# connectors.net
KiCad netlist of a schematic drawn in Altium Designer
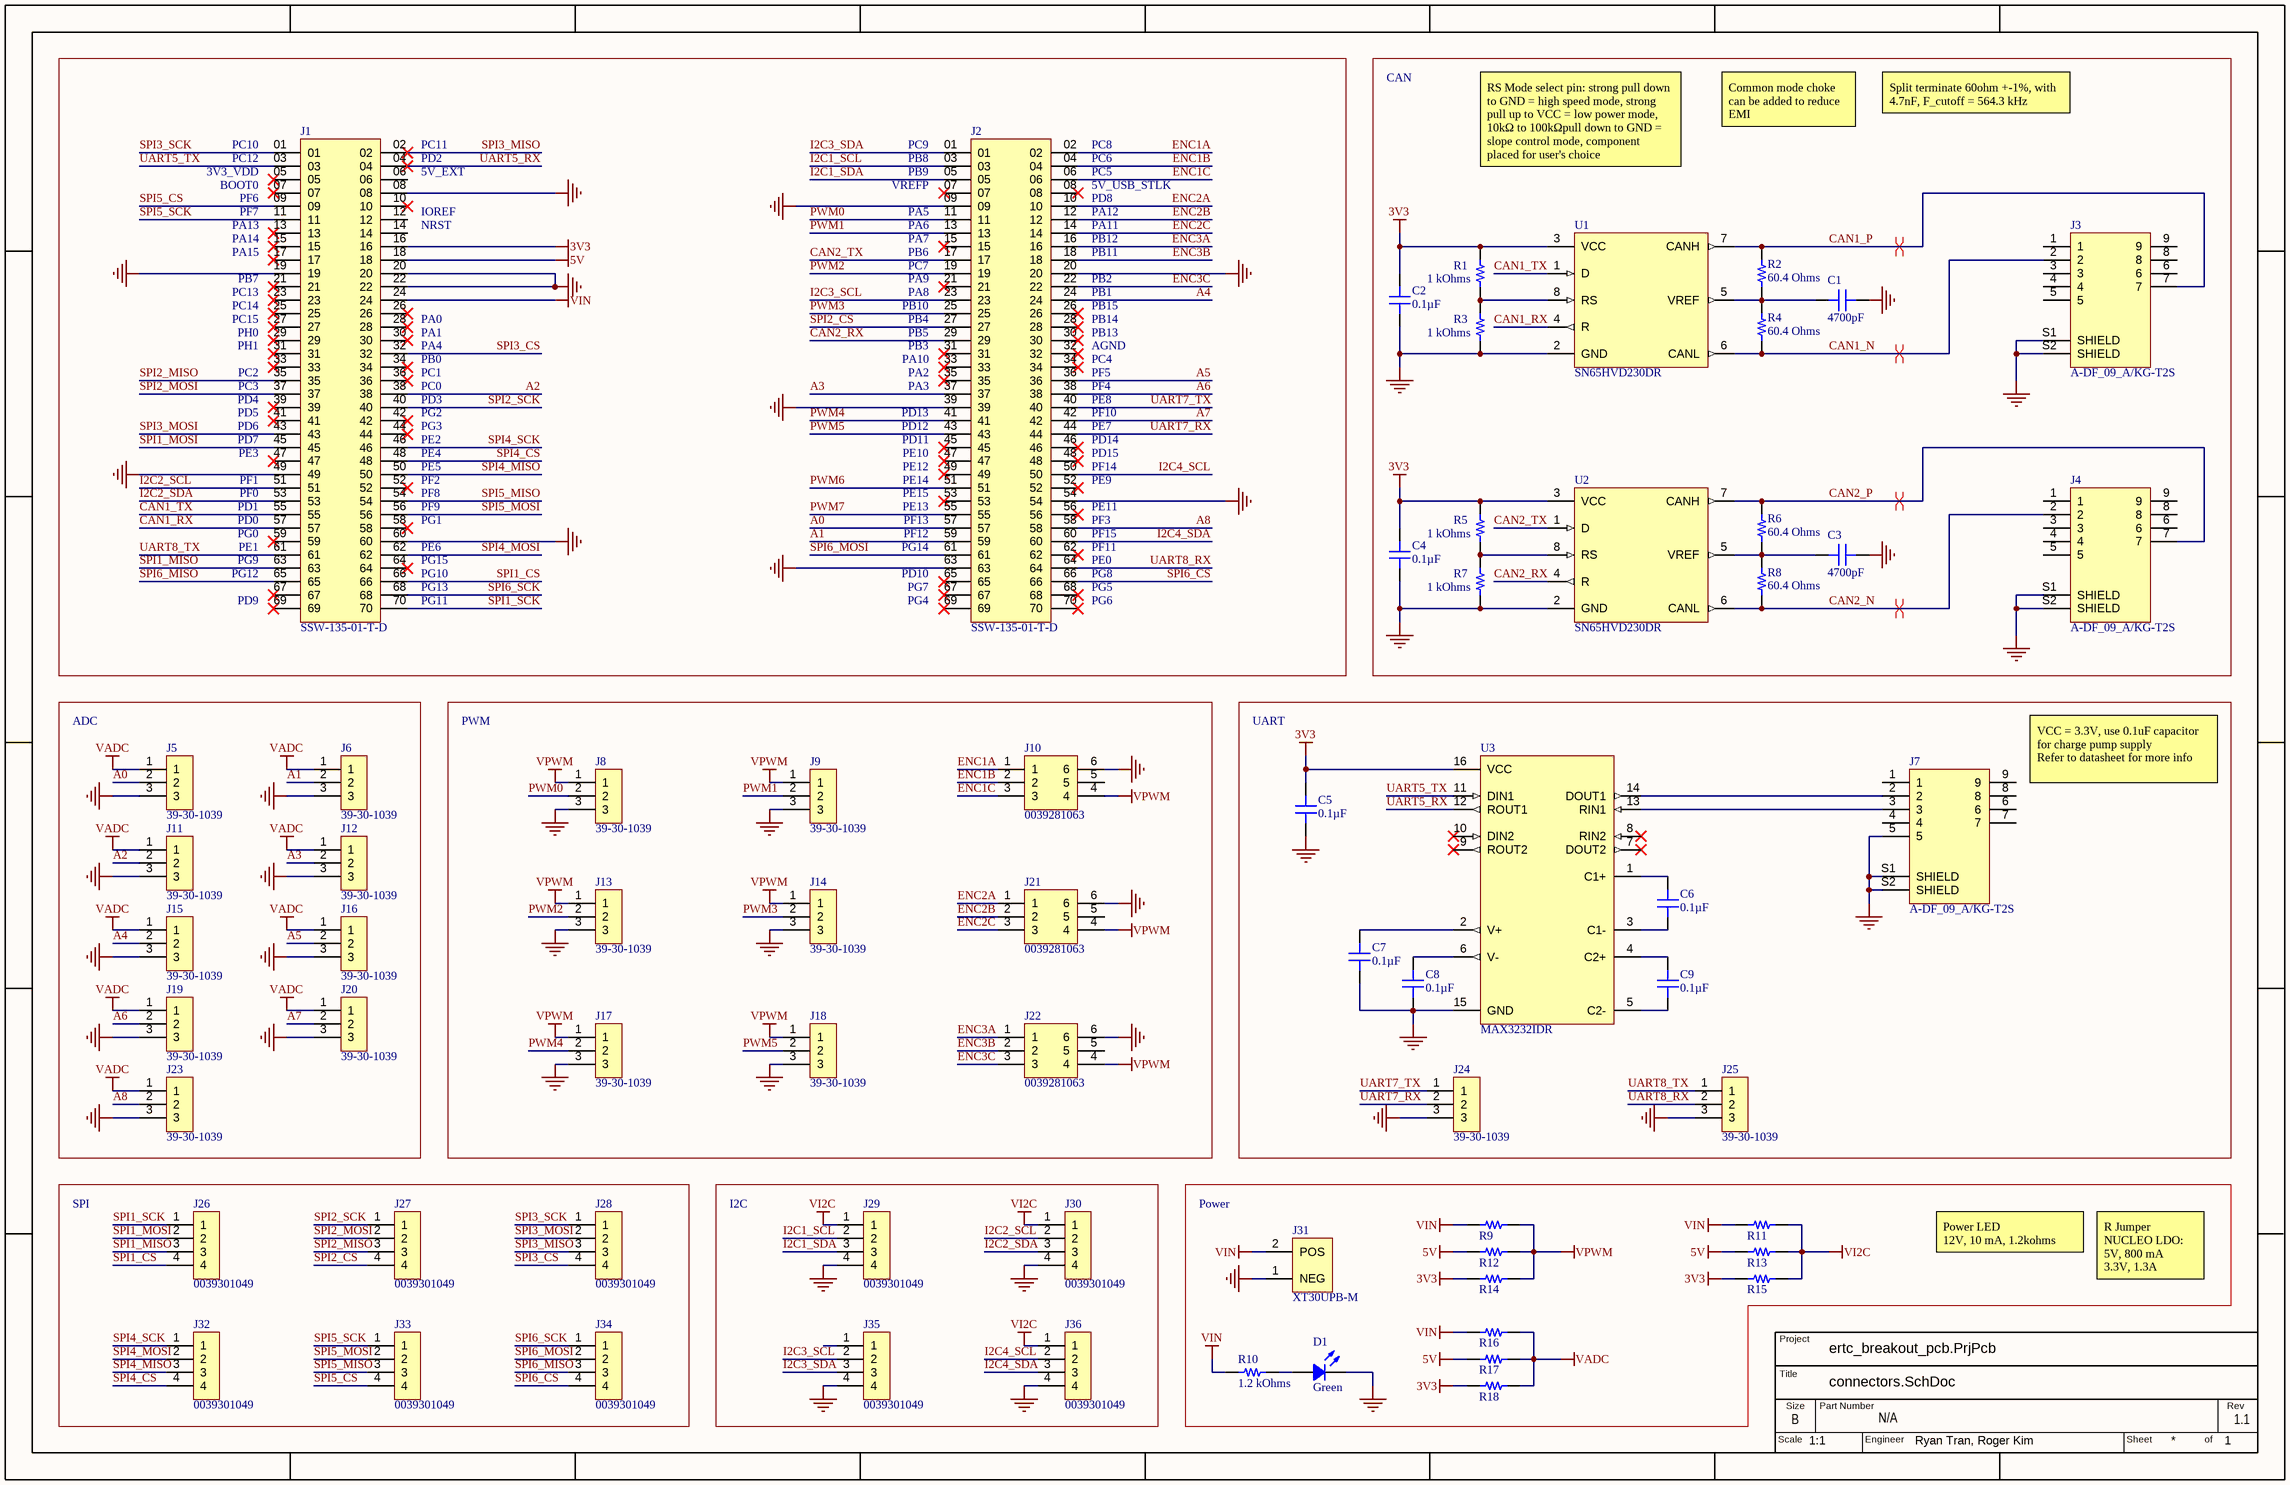
[diagram p0: connectors.SchDoc]

(export (version "E")
  (design (tool "Eeschema 10.0.6"))
  (components
    (comp (ref "C1")
      (value "4700pF")
      (footprint "CAP 0603_1608")
      (description "CAP CER 4700PF 50V X7R 0603")
      (fields
        (field (name "PART NUMBER") "CGA3E2X7R1H472K080AA")
        (field (name "MANUFACTURER") "TDK Corporation")
      )
      (libsource (lib "Celestial Altium Library - altium_library") (part "Capacitor"))
    )
    (comp (ref "C2")
      (value "0.1µF")
      (footprint "CAP 0603_1608")
      (description "CAP CER 0.1UF 25V X7R 0603")
      (fields
        (field (name "PART NUMBER") "CL10B104KA8NNNC")
        (field (name "MANUFACTURER") "Samsung Electro-Mechanics")
      )
      (libsource (lib "Celestial Altium Library - altium_library") (part "Capacitor"))
    )
    (comp (ref "C3")
      (value "4700pF")
      (footprint "CAP 0603_1608")
      (description "CAP CER 4700PF 50V X7R 0603")
      (fields
        (field (name "PART NUMBER") "CGA3E2X7R1H472K080AA")
        (field (name "MANUFACTURER") "TDK Corporation")
      )
      (libsource (lib "Celestial Altium Library - altium_library") (part "Capacitor"))
    )
    (comp (ref "C4")
      (value "0.1µF")
      (footprint "CAP 0603_1608")
      (description "CAP CER 0.1UF 25V X7R 0603")
      (fields
        (field (name "PART NUMBER") "CL10B104KA8NNNC")
        (field (name "MANUFACTURER") "Samsung Electro-Mechanics")
      )
      (libsource (lib "Celestial Altium Library - altium_library") (part "Capacitor"))
    )
    (comp (ref "C5")
      (value "0.1µF")
      (footprint "CAP 0603_1608")
      (description "CAP CER 0.1UF 25V X7R 0603")
      (fields
        (field (name "PART NUMBER") "CL10B104KA8NNNC")
        (field (name "MANUFACTURER") "Samsung Electro-Mechanics")
      )
      (libsource (lib "Celestial Altium Library - altium_library") (part "Capacitor"))
    )
    (comp (ref "C6")
      (value "0.1µF")
      (footprint "CAP 0603_1608")
      (description "CAP CER 0.1UF 25V X7R 0603")
      (fields
        (field (name "PART NUMBER") "CL10B104KA8NNNC")
        (field (name "MANUFACTURER") "Samsung Electro-Mechanics")
      )
      (libsource (lib "Celestial Altium Library - altium_library") (part "Capacitor"))
    )
    (comp (ref "C7")
      (value "0.1µF")
      (footprint "CAP 0603_1608")
      (description "CAP CER 0.1UF 25V X7R 0603")
      (fields
        (field (name "PART NUMBER") "CL10B104KA8NNNC")
        (field (name "MANUFACTURER") "Samsung Electro-Mechanics")
      )
      (libsource (lib "Celestial Altium Library - altium_library") (part "Capacitor"))
    )
    (comp (ref "C8")
      (value "0.1µF")
      (footprint "CAP 0603_1608")
      (description "CAP CER 0.1UF 25V X7R 0603")
      (fields
        (field (name "PART NUMBER") "CL10B104KA8NNNC")
        (field (name "MANUFACTURER") "Samsung Electro-Mechanics")
      )
      (libsource (lib "Celestial Altium Library - altium_library") (part "Capacitor"))
    )
    (comp (ref "C9")
      (value "0.1µF")
      (footprint "CAP 0603_1608")
      (description "CAP CER 0.1UF 25V X7R 0603")
      (fields
        (field (name "PART NUMBER") "CL10B104KA8NNNC")
        (field (name "MANUFACTURER") "Samsung Electro-Mechanics")
      )
      (libsource (lib "Celestial Altium Library - altium_library") (part "Capacitor"))
    )
    (comp (ref "D1")
      (value "Green")
      (footprint "LED 0805_2012 GREEN")
      (description "LED GREEN CLEAR SMD")
      (fields (field (name "PART NUMBER") "LTST-C170GKT") (field (name "MANUFACTURER") "Lite-On Inc."))
      (libsource (lib "Celestial Altium Library - altium_library") (part "LED"))
    )
    (comp (ref "J1")
      (value "SSW-135-01-T-D")
      (footprint "SAMTEC_SSW-135-01-T-D")
      (fields (field (name "MF") "Samtec"))
      (libsource (lib "ertc_symbols") (part "SSW-135-01-T-D"))
    )
    (comp (ref "J2")
      (value "SSW-135-01-T-D")
      (footprint "SAMTEC_SSW-135-01-T-D")
      (fields (field (name "MF") "Samtec"))
      (libsource (lib "ertc_symbols") (part "SSW-135-01-T-D"))
    )
    (comp (ref "J3")
      (value "A-DF_09_A/KG-T2S")
      (footprint "ASSMANN_A-DF09A/KG-T2S")
      (description "9 Position D-Sub Receptacle, Female Sockets Connector")
      (fields (field (name "MP") "A-DF 09 A/KG-T2S") (field (name "MF") "Assmann WSW"))
      (libsource (lib "ertc_symbols") (part "A-DF_09_A/KG-T2S"))
    )
    (comp (ref "J4")
      (value "A-DF_09_A/KG-T2S")
      (footprint "ASSMANN_A-DF09A/KG-T2S")
      (description "9 Position D-Sub Receptacle, Female Sockets Connector")
      (fields (field (name "MP") "A-DF 09 A/KG-T2S") (field (name "MF") "Assmann WSW"))
      (libsource (lib "ertc_symbols") (part "A-DF_09_A/KG-T2S"))
    )
    (comp (ref "J5")
      (value "39-30-1039")
      (footprint "MOLEX_39-30-1039")
      (description "Connector Header Through Hole 3 position 0.165 _4.20mm_")
      (fields (field (name "MP") "39301039") (field (name "MF") "Molex"))
      (libsource (lib "ertc_symbols") (part "39-30-1039"))
    )
    (comp (ref "J6")
      (value "39-30-1039")
      (footprint "MOLEX_39-30-1039")
      (description "Connector Header Through Hole 3 position 0.165 _4.20mm_")
      (fields (field (name "MP") "39301039") (field (name "MF") "Molex"))
      (libsource (lib "ertc_symbols") (part "39-30-1039"))
    )
    (comp (ref "J7")
      (value "A-DF_09_A/KG-T2S")
      (footprint "ASSMANN_A-DF09A/KG-T2S")
      (description "9 Position D-Sub Receptacle, Female Sockets Connector")
      (fields (field (name "MP") "A-DF 09 A/KG-T2S") (field (name "MF") "Assmann WSW"))
      (libsource (lib "ertc_symbols") (part "A-DF_09_A/KG-T2S"))
    )
    (comp (ref "J8")
      (value "39-30-1039")
      (footprint "MOLEX_39-30-1039")
      (description "Connector Header Through Hole 3 position 0.165 _4.20mm_")
      (fields (field (name "MP") "39301039") (field (name "MF") "Molex"))
      (libsource (lib "ertc_symbols") (part "39-30-1039"))
    )
    (comp (ref "J9")
      (value "39-30-1039")
      (footprint "MOLEX_39-30-1039")
      (description "Connector Header Through Hole 3 position 0.165 _4.20mm_")
      (fields (field (name "MP") "39301039") (field (name "MF") "Molex"))
      (libsource (lib "ertc_symbols") (part "39-30-1039"))
    )
    (comp (ref "J10")
      (value "0039281063")
      (footprint "MOLEX_0039281063")
      (description "Connector Header Through Hole, 6 position 0.165 (4.20mm)")
      (fields (field (name "MP") "0026013115") (field (name "MF") "Molex"))
      (libsource (lib "ertc_symbols") (part "0039281063"))
    )
    (comp (ref "J11")
      (value "39-30-1039")
      (footprint "MOLEX_39-30-1039")
      (description "Connector Header Through Hole 3 position 0.165 _4.20mm_")
      (fields (field (name "MP") "39301039") (field (name "MF") "Molex"))
      (libsource (lib "ertc_symbols") (part "39-30-1039"))
    )
    (comp (ref "J12")
      (value "39-30-1039")
      (footprint "MOLEX_39-30-1039")
      (description "Connector Header Through Hole 3 position 0.165 _4.20mm_")
      (fields (field (name "MP") "39301039") (field (name "MF") "Molex"))
      (libsource (lib "ertc_symbols") (part "39-30-1039"))
    )
    (comp (ref "J13")
      (value "39-30-1039")
      (footprint "MOLEX_39-30-1039")
      (description "Connector Header Through Hole 3 position 0.165 _4.20mm_")
      (fields (field (name "MP") "39301039") (field (name "MF") "Molex"))
      (libsource (lib "ertc_symbols") (part "39-30-1039"))
    )
    (comp (ref "J14")
      (value "39-30-1039")
      (footprint "MOLEX_39-30-1039")
      (description "Connector Header Through Hole 3 position 0.165 _4.20mm_")
      (fields (field (name "MP") "39301039") (field (name "MF") "Molex"))
      (libsource (lib "ertc_symbols") (part "39-30-1039"))
    )
    (comp (ref "J15")
      (value "39-30-1039")
      (footprint "MOLEX_39-30-1039")
      (description "Connector Header Through Hole 3 position 0.165 _4.20mm_")
      (fields (field (name "MP") "39301039") (field (name "MF") "Molex"))
      (libsource (lib "ertc_symbols") (part "39-30-1039"))
    )
    (comp (ref "J16")
      (value "39-30-1039")
      (footprint "MOLEX_39-30-1039")
      (description "Connector Header Through Hole 3 position 0.165 _4.20mm_")
      (fields (field (name "MP") "39301039") (field (name "MF") "Molex"))
      (libsource (lib "ertc_symbols") (part "39-30-1039"))
    )
    (comp (ref "J17")
      (value "39-30-1039")
      (footprint "MOLEX_39-30-1039")
      (description "Connector Header Through Hole 3 position 0.165 _4.20mm_")
      (fields (field (name "MP") "39301039") (field (name "MF") "Molex"))
      (libsource (lib "ertc_symbols") (part "39-30-1039"))
    )
    (comp (ref "J18")
      (value "39-30-1039")
      (footprint "MOLEX_39-30-1039")
      (description "Connector Header Through Hole 3 position 0.165 _4.20mm_")
      (fields (field (name "MP") "39301039") (field (name "MF") "Molex"))
      (libsource (lib "ertc_symbols") (part "39-30-1039"))
    )
    (comp (ref "J19")
      (value "39-30-1039")
      (footprint "MOLEX_39-30-1039")
      (description "Connector Header Through Hole 3 position 0.165 _4.20mm_")
      (fields (field (name "MP") "39301039") (field (name "MF") "Molex"))
      (libsource (lib "ertc_symbols") (part "39-30-1039"))
    )
    (comp (ref "J20")
      (value "39-30-1039")
      (footprint "MOLEX_39-30-1039")
      (description "Connector Header Through Hole 3 position 0.165 _4.20mm_")
      (fields (field (name "MP") "39301039") (field (name "MF") "Molex"))
      (libsource (lib "ertc_symbols") (part "39-30-1039"))
    )
    (comp (ref "J21")
      (value "0039281063")
      (footprint "MOLEX_0039281063")
      (description "Connector Header Through Hole, 6 position 0.165 (4.20mm)")
      (fields (field (name "MP") "0026013115") (field (name "MF") "Molex"))
      (libsource (lib "ertc_symbols") (part "0039281063"))
    )
    (comp (ref "J22")
      (value "0039281063")
      (footprint "MOLEX_0039281063")
      (description "Connector Header Through Hole, 6 position 0.165 (4.20mm)")
      (fields (field (name "MP") "0026013115") (field (name "MF") "Molex"))
      (libsource (lib "ertc_symbols") (part "0039281063"))
    )
    (comp (ref "J23")
      (value "39-30-1039")
      (footprint "MOLEX_39-30-1039")
      (description "Connector Header Through Hole 3 position 0.165 _4.20mm_")
      (fields (field (name "MP") "39301039") (field (name "MF") "Molex"))
      (libsource (lib "ertc_symbols") (part "39-30-1039"))
    )
    (comp (ref "J24")
      (value "39-30-1039")
      (footprint "MOLEX_39-30-1039")
      (description "Connector Header Through Hole 3 position 0.165 _4.20mm_")
      (fields (field (name "MP") "39301039") (field (name "MF") "Molex"))
      (libsource (lib "ertc_symbols") (part "39-30-1039"))
    )
    (comp (ref "J25")
      (value "39-30-1039")
      (footprint "MOLEX_39-30-1039")
      (description "Connector Header Through Hole 3 position 0.165 _4.20mm_")
      (fields (field (name "MP") "39301039") (field (name "MF") "Molex"))
      (libsource (lib "ertc_symbols") (part "39-30-1039"))
    )
    (comp (ref "J26")
      (value "0039301049")
      (footprint "MOLEX_0039301049")
      (description "Connector Header Through Hole 4 position 0.165 _4.20mm_")
      (fields (field (name "MF") "Molex"))
      (libsource (lib "ertc_symbols") (part "0039301049"))
    )
    (comp (ref "J27")
      (value "0039301049")
      (footprint "MOLEX_0039301049")
      (description "Connector Header Through Hole 4 position 0.165 _4.20mm_")
      (fields (field (name "MF") "Molex"))
      (libsource (lib "ertc_symbols") (part "0039301049"))
    )
    (comp (ref "J28")
      (value "0039301049")
      (footprint "MOLEX_0039301049")
      (description "Connector Header Through Hole 4 position 0.165 _4.20mm_")
      (fields (field (name "MF") "Molex"))
      (libsource (lib "ertc_symbols") (part "0039301049"))
    )
    (comp (ref "J29")
      (value "0039301049")
      (footprint "MOLEX_0039301049")
      (description "Connector Header Through Hole 4 position 0.165 _4.20mm_")
      (fields (field (name "MF") "Molex"))
      (libsource (lib "ertc_symbols") (part "0039301049"))
    )
    (comp (ref "J30")
      (value "0039301049")
      (footprint "MOLEX_0039301049")
      (description "Connector Header Through Hole 4 position 0.165 _4.20mm_")
      (fields (field (name "MF") "Molex"))
      (libsource (lib "ertc_symbols") (part "0039301049"))
    )
    (comp (ref "J31")
      (value "XT30UPB-M")
      (footprint "AMASS_XT30-M")
      (description "Plug; DC supply; XT60; male; PIN: 2; for cable; soldered; 30A; 500V")
      (fields (field (name "MP") "XT60-M") (field (name "MF") "AMASS"))
      (libsource (lib "ertc_symbols") (part "XT30UPB-M"))
    )
    (comp (ref "J32")
      (value "0039301049")
      (footprint "MOLEX_0039301049")
      (description "Connector Header Through Hole 4 position 0.165 _4.20mm_")
      (fields (field (name "MF") "Molex"))
      (libsource (lib "ertc_symbols") (part "0039301049"))
    )
    (comp (ref "J33")
      (value "0039301049")
      (footprint "MOLEX_0039301049")
      (description "Connector Header Through Hole 4 position 0.165 _4.20mm_")
      (fields (field (name "MF") "Molex"))
      (libsource (lib "ertc_symbols") (part "0039301049"))
    )
    (comp (ref "J34")
      (value "0039301049")
      (footprint "MOLEX_0039301049")
      (description "Connector Header Through Hole 4 position 0.165 _4.20mm_")
      (fields (field (name "MF") "Molex"))
      (libsource (lib "ertc_symbols") (part "0039301049"))
    )
    (comp (ref "J35")
      (value "0039301049")
      (footprint "MOLEX_0039301049")
      (description "Connector Header Through Hole 4 position 0.165 _4.20mm_")
      (fields (field (name "MF") "Molex"))
      (libsource (lib "ertc_symbols") (part "0039301049"))
    )
    (comp (ref "J36")
      (value "0039301049")
      (footprint "MOLEX_0039301049")
      (description "Connector Header Through Hole 4 position 0.165 _4.20mm_")
      (fields (field (name "MF") "Molex"))
      (libsource (lib "ertc_symbols") (part "0039301049"))
    )
    (comp (ref "R1")
      (value "1 kOhms")
      (footprint "RES 0805_2012")
      (description "RES 1K OHM 1% 1/4W 0805")
      (fields
        (field (name "PART NUMBER") "RNCP0805FTD1K00")
        (field (name "MANUFACTURER") "Stackpole Electronics Inc")
      )
      (libsource (lib "Celestial Altium Library - altium_library") (part "Resistor"))
    )
    (comp (ref "R2")
      (value "60.4 Ohms")
      (footprint "RES 0603_1608")
      (description "RES 60.4 OHM 1% 1/10W 0603")
      (fields
        (field (name "PART NUMBER") "RMCF0603FT60R4")
        (field (name "MANUFACTURER") "Stackpole Electronics Inc")
      )
      (libsource (lib "Celestial Altium Library - altium_library") (part "Resistor"))
    )
    (comp (ref "R3")
      (value "1 kOhms")
      (footprint "RES 0805_2012")
      (description "RES 1K OHM 1% 1/4W 0805")
      (fields
        (field (name "PART NUMBER") "RNCP0805FTD1K00")
        (field (name "MANUFACTURER") "Stackpole Electronics Inc")
      )
      (libsource (lib "Celestial Altium Library - altium_library") (part "Resistor"))
    )
    (comp (ref "R4")
      (value "60.4 Ohms")
      (footprint "RES 0603_1608")
      (description "RES 60.4 OHM 1% 1/10W 0603")
      (fields
        (field (name "PART NUMBER") "RMCF0603FT60R4")
        (field (name "MANUFACTURER") "Stackpole Electronics Inc")
      )
      (libsource (lib "Celestial Altium Library - altium_library") (part "Resistor"))
    )
    (comp (ref "R5")
      (value "1 kOhms")
      (footprint "RES 0805_2012")
      (description "RES 1K OHM 1% 1/4W 0805")
      (fields
        (field (name "PART NUMBER") "RNCP0805FTD1K00")
        (field (name "MANUFACTURER") "Stackpole Electronics Inc")
      )
      (libsource (lib "Celestial Altium Library - altium_library") (part "Resistor"))
    )
    (comp (ref "R6")
      (value "60.4 Ohms")
      (footprint "RES 0603_1608")
      (description "RES 60.4 OHM 1% 1/10W 0603")
      (fields
        (field (name "PART NUMBER") "RMCF0603FT60R4")
        (field (name "MANUFACTURER") "Stackpole Electronics Inc")
      )
      (libsource (lib "Celestial Altium Library - altium_library") (part "Resistor"))
    )
    (comp (ref "R7")
      (value "1 kOhms")
      (footprint "RES 0805_2012")
      (description "RES 1K OHM 1% 1/4W 0805")
      (fields
        (field (name "PART NUMBER") "RNCP0805FTD1K00")
        (field (name "MANUFACTURER") "Stackpole Electronics Inc")
      )
      (libsource (lib "Celestial Altium Library - altium_library") (part "Resistor"))
    )
    (comp (ref "R8")
      (value "60.4 Ohms")
      (footprint "RES 0603_1608")
      (description "RES 60.4 OHM 1% 1/10W 0603")
      (fields
        (field (name "PART NUMBER") "RMCF0603FT60R4")
        (field (name "MANUFACTURER") "Stackpole Electronics Inc")
      )
      (libsource (lib "Celestial Altium Library - altium_library") (part "Resistor"))
    )
    (comp (ref "R9")
      (value "~")
      (footprint "RES 0603_1608")
      (description "RES SMD 0 OHM JUMP 1/10W 0603")
      (fields (field (name "PART NUMBER") "CRCW06030000Z0EBC") (field (name "MANUFACTURER") "Vishay Dale"))
      (libsource (lib "Celestial Altium Library - altium_library") (part "Resistor"))
    )
    (comp (ref "R10")
      (value "1.2 kOhms")
      (footprint "RES 0603_1608")
      (description "CRGCQ 0603 1K2 1%")
      (fields
        (field (name "PART NUMBER") "CRGCQ0603F1K2")
        (field (name "MANUFACTURER") "TE Connectivity Passive Product")
      )
      (libsource (lib "Celestial Altium Library - altium_library") (part "Resistor"))
    )
    (comp (ref "R11")
      (value "~")
      (footprint "RES 0603_1608")
      (description "RES SMD 0 OHM JUMP 1/10W 0603")
      (fields (field (name "PART NUMBER") "CRCW06030000Z0EBC") (field (name "MANUFACTURER") "Vishay Dale"))
      (libsource (lib "Celestial Altium Library - altium_library") (part "Resistor"))
    )
    (comp (ref "R12")
      (value "~")
      (footprint "RES 0603_1608")
      (description "RES SMD 0 OHM JUMP 1/10W 0603")
      (fields (field (name "PART NUMBER") "CRCW06030000Z0EBC") (field (name "MANUFACTURER") "Vishay Dale"))
      (libsource (lib "Celestial Altium Library - altium_library") (part "Resistor"))
    )
    (comp (ref "R13")
      (value "~")
      (footprint "RES 0603_1608")
      (description "RES SMD 0 OHM JUMP 1/10W 0603")
      (fields (field (name "PART NUMBER") "CRCW06030000Z0EBC") (field (name "MANUFACTURER") "Vishay Dale"))
      (libsource (lib "Celestial Altium Library - altium_library") (part "Resistor"))
    )
    (comp (ref "R14")
      (value "~")
      (footprint "RES 0603_1608")
      (description "RES SMD 0 OHM JUMP 1/10W 0603")
      (fields (field (name "PART NUMBER") "CRCW06030000Z0EBC") (field (name "MANUFACTURER") "Vishay Dale"))
      (libsource (lib "Celestial Altium Library - altium_library") (part "Resistor"))
    )
    (comp (ref "R15")
      (value "~")
      (footprint "RES 0603_1608")
      (description "RES SMD 0 OHM JUMP 1/10W 0603")
      (fields (field (name "PART NUMBER") "CRCW06030000Z0EBC") (field (name "MANUFACTURER") "Vishay Dale"))
      (libsource (lib "Celestial Altium Library - altium_library") (part "Resistor"))
    )
    (comp (ref "R16")
      (value "~")
      (footprint "RES 0603_1608")
      (description "RES SMD 0 OHM JUMP 1/10W 0603")
      (fields (field (name "PART NUMBER") "CRCW06030000Z0EBC") (field (name "MANUFACTURER") "Vishay Dale"))
      (libsource (lib "Celestial Altium Library - altium_library") (part "Resistor"))
    )
    (comp (ref "R17")
      (value "~")
      (footprint "RES 0603_1608")
      (description "RES SMD 0 OHM JUMP 1/10W 0603")
      (fields (field (name "PART NUMBER") "CRCW06030000Z0EBC") (field (name "MANUFACTURER") "Vishay Dale"))
      (libsource (lib "Celestial Altium Library - altium_library") (part "Resistor"))
    )
    (comp (ref "R18")
      (value "~")
      (footprint "RES 0603_1608")
      (description "RES SMD 0 OHM JUMP 1/10W 0603")
      (fields (field (name "PART NUMBER") "CRCW06030000Z0EBC") (field (name "MANUFACTURER") "Vishay Dale"))
      (libsource (lib "Celestial Altium Library - altium_library") (part "Resistor"))
    )
    (comp (ref "U1")
      (value "SN65HVD230DR")
      (footprint "SOIC127P599X175-8N")
      (description "3.3 V CAN Transceiver with Standby Mode 8-SOIC -40 to 85")
      (fields (field (name "MF") "Texas Instruments"))
      (libsource (lib "ertc_symbols") (part "SN65HVD230DR"))
    )
    (comp (ref "U2")
      (value "SN65HVD230DR")
      (footprint "SOIC127P599X175-8N")
      (description "3.3 V CAN Transceiver with Standby Mode 8-SOIC -40 to 85")
      (fields (field (name "MF") "Texas Instruments"))
      (libsource (lib "ertc_symbols") (part "SN65HVD230DR"))
    )
    (comp (ref "U3")
      (value "MAX3232IDR")
      (footprint "SOIC127P600X175-16N")
      (description "3-V to 5.5-V multichannel RS-232 line driver & receiver 16-SOIC -40 to 85")
      (fields (field (name "MF") "Texas Instruments") (field (name "DIGI-KEY_PART_NUMBER") "296-13098-1-ND"))
      (libsource (lib "ertc_symbols") (part "MAX3232IDR"))
    )
  )
  (nets
    (net (code "2") (name "/A0") (class "Default")
      (node (ref "J2") (pin "57") (pinfunction "57_57") (pintype "passive"))
      (node (ref "J5") (pin "2") (pinfunction "2_2") (pintype "passive"))
    )
    (net (code "3") (name "/A1") (class "Default")
      (node (ref "J2") (pin "59") (pinfunction "59_59") (pintype "passive"))
      (node (ref "J6") (pin "2") (pinfunction "2_2") (pintype "passive"))
    )
    (net (code "4") (name "/A2") (class "Default")
      (node (ref "J1") (pin "38") (pinfunction "38_38") (pintype "passive"))
      (node (ref "J11") (pin "2") (pinfunction "2_2") (pintype "passive"))
    )
    (net (code "5") (name "/A3") (class "Default")
      (node (ref "J12") (pin "2") (pinfunction "2_2") (pintype "passive"))
      (node (ref "J2") (pin "37") (pinfunction "37_37") (pintype "passive"))
    )
    (net (code "6") (name "/A4") (class "Default")
      (node (ref "J15") (pin "2") (pinfunction "2_2") (pintype "passive"))
      (node (ref "J2") (pin "24") (pinfunction "24_24") (pintype "passive"))
    )
    (net (code "7") (name "/A5") (class "Default")
      (node (ref "J16") (pin "2") (pinfunction "2_2") (pintype "passive"))
      (node (ref "J2") (pin "36") (pinfunction "36_36") (pintype "passive"))
    )
    (net (code "8") (name "/A6") (class "Default")
      (node (ref "J19") (pin "2") (pinfunction "2_2") (pintype "passive"))
      (node (ref "J2") (pin "38") (pinfunction "38_38") (pintype "passive"))
    )
    (net (code "9") (name "/A7") (class "Default")
      (node (ref "J2") (pin "42") (pinfunction "42_42") (pintype "passive"))
      (node (ref "J20") (pin "2") (pinfunction "2_2") (pintype "passive"))
    )
    (net (code "10") (name "/A8") (class "Default")
      (node (ref "J2") (pin "58") (pinfunction "58_58") (pintype "passive"))
      (node (ref "J23") (pin "2") (pinfunction "2_2") (pintype "passive"))
    )
    (net (code "11") (name "/CAN1_N") (class "Default")
      (node (ref "J3") (pin "2") (pinfunction "2_2") (pintype "passive"))
      (node (ref "R4") (pin "2") (pinfunction "2_2") (pintype "passive"))
      (node (ref "U1") (pin "6") (pinfunction "CANL_6") (pintype "output"))
    )
    (net (code "12") (name "/CAN1_P") (class "Default")
      (node (ref "J3") (pin "7") (pinfunction "7_7") (pintype "passive"))
      (node (ref "R2") (pin "1") (pinfunction "1_1") (pintype "passive"))
      (node (ref "U1") (pin "7") (pinfunction "CANH_7") (pintype "output"))
    )
    (net (code "13") (name "/CAN1_RX") (class "Default")
      (node (ref "J1") (pin "57") (pinfunction "57_57") (pintype "passive"))
      (node (ref "U1") (pin "4") (pinfunction "R_4") (pintype "output"))
    )
    (net (code "14") (name "/CAN1_TX") (class "Default")
      (node (ref "J1") (pin "55") (pinfunction "55_55") (pintype "passive"))
      (node (ref "U1") (pin "1") (pinfunction "D_1") (pintype "input"))
    )
    (net (code "15") (name "/CAN2_N") (class "Default")
      (node (ref "J4") (pin "2") (pinfunction "2_2") (pintype "passive"))
      (node (ref "R8") (pin "2") (pinfunction "2_2") (pintype "passive"))
      (node (ref "U2") (pin "6") (pinfunction "CANL_6") (pintype "output"))
    )
    (net (code "16") (name "/CAN2_P") (class "Default")
      (node (ref "J4") (pin "7") (pinfunction "7_7") (pintype "passive"))
      (node (ref "R6") (pin "1") (pinfunction "1_1") (pintype "passive"))
      (node (ref "U2") (pin "7") (pinfunction "CANH_7") (pintype "output"))
    )
    (net (code "17") (name "/CAN2_RX") (class "Default")
      (node (ref "J2") (pin "29") (pinfunction "29_29") (pintype "passive"))
      (node (ref "U2") (pin "4") (pinfunction "R_4") (pintype "output"))
    )
    (net (code "18") (name "/CAN2_TX") (class "Default")
      (node (ref "J2") (pin "17") (pinfunction "17_17") (pintype "passive"))
      (node (ref "U2") (pin "1") (pinfunction "D_1") (pintype "input"))
    )
    (net (code "19") (name "/ENC1A") (class "Default")
      (node (ref "J10") (pin "1") (pinfunction "1_1") (pintype "passive"))
      (node (ref "J2") (pin "02") (pinfunction "02_02") (pintype "passive"))
    )
    (net (code "20") (name "/ENC1B") (class "Default")
      (node (ref "J10") (pin "2") (pinfunction "2_2") (pintype "passive"))
      (node (ref "J2") (pin "04") (pinfunction "04_04") (pintype "passive"))
    )
    (net (code "21") (name "/ENC1C") (class "Default")
      (node (ref "J10") (pin "3") (pinfunction "3_3") (pintype "passive"))
      (node (ref "J2") (pin "06") (pinfunction "06_06") (pintype "passive"))
    )
    (net (code "22") (name "/ENC2A") (class "Default")
      (node (ref "J2") (pin "10") (pinfunction "10_10") (pintype "passive"))
      (node (ref "J21") (pin "1") (pinfunction "1_1") (pintype "passive"))
    )
    (net (code "23") (name "/ENC2B") (class "Default")
      (node (ref "J2") (pin "12") (pinfunction "12_12") (pintype "passive"))
      (node (ref "J21") (pin "2") (pinfunction "2_2") (pintype "passive"))
    )
    (net (code "24") (name "/ENC2C") (class "Default")
      (node (ref "J2") (pin "14") (pinfunction "14_14") (pintype "passive"))
      (node (ref "J21") (pin "3") (pinfunction "3_3") (pintype "passive"))
    )
    (net (code "25") (name "/ENC3A") (class "Default")
      (node (ref "J2") (pin "16") (pinfunction "16_16") (pintype "passive"))
      (node (ref "J22") (pin "1") (pinfunction "1_1") (pintype "passive"))
    )
    (net (code "26") (name "/ENC3B") (class "Default")
      (node (ref "J2") (pin "18") (pinfunction "18_18") (pintype "passive"))
      (node (ref "J22") (pin "2") (pinfunction "2_2") (pintype "passive"))
    )
    (net (code "27") (name "/ENC3C") (class "Default")
      (node (ref "J2") (pin "22") (pinfunction "22_22") (pintype "passive"))
      (node (ref "J22") (pin "3") (pinfunction "3_3") (pintype "passive"))
    )
    (net (code "28") (name "/I2C1_SCL") (class "Default")
      (node (ref "J2") (pin "03") (pinfunction "03_03") (pintype "passive"))
      (node (ref "J29") (pin "2") (pinfunction "2_2") (pintype "passive"))
    )
    (net (code "29") (name "/I2C1_SDA") (class "Default")
      (node (ref "J2") (pin "05") (pinfunction "05_05") (pintype "passive"))
      (node (ref "J29") (pin "3") (pinfunction "3_3") (pintype "passive"))
    )
    (net (code "30") (name "/I2C2_SCL") (class "Default")
      (node (ref "J1") (pin "51") (pinfunction "51_51") (pintype "passive"))
      (node (ref "J30") (pin "2") (pinfunction "2_2") (pintype "passive"))
    )
    (net (code "31") (name "/I2C2_SDA") (class "Default")
      (node (ref "J1") (pin "53") (pinfunction "53_53") (pintype "passive"))
      (node (ref "J30") (pin "3") (pinfunction "3_3") (pintype "passive"))
    )
    (net (code "32") (name "/I2C3_SCL") (class "Default")
      (node (ref "J2") (pin "23") (pinfunction "23_23") (pintype "passive"))
      (node (ref "J35") (pin "2") (pinfunction "2_2") (pintype "passive"))
    )
    (net (code "33") (name "/I2C3_SDA") (class "Default")
      (node (ref "J2") (pin "01") (pinfunction "01_01") (pintype "passive"))
      (node (ref "J35") (pin "3") (pinfunction "3_3") (pintype "passive"))
    )
    (net (code "34") (name "/I2C4_SCL") (class "Default")
      (node (ref "J2") (pin "50") (pinfunction "50_50") (pintype "passive"))
      (node (ref "J36") (pin "2") (pinfunction "2_2") (pintype "passive"))
    )
    (net (code "35") (name "/I2C4_SDA") (class "Default")
      (node (ref "J2") (pin "60") (pinfunction "60_60") (pintype "passive"))
      (node (ref "J36") (pin "3") (pinfunction "3_3") (pintype "passive"))
    )
    (net (code "36") (name "/PWM0") (class "Default")
      (node (ref "J2") (pin "11") (pinfunction "11_11") (pintype "passive"))
      (node (ref "J8") (pin "2") (pinfunction "2_2") (pintype "passive"))
    )
    (net (code "37") (name "/PWM1") (class "Default")
      (node (ref "J2") (pin "13") (pinfunction "13_13") (pintype "passive"))
      (node (ref "J9") (pin "2") (pinfunction "2_2") (pintype "passive"))
    )
    (net (code "38") (name "/PWM2") (class "Default")
      (node (ref "J13") (pin "2") (pinfunction "2_2") (pintype "passive"))
      (node (ref "J2") (pin "19") (pinfunction "19_19") (pintype "passive"))
    )
    (net (code "39") (name "/PWM3") (class "Default")
      (node (ref "J14") (pin "2") (pinfunction "2_2") (pintype "passive"))
      (node (ref "J2") (pin "25") (pinfunction "25_25") (pintype "passive"))
    )
    (net (code "40") (name "/PWM4") (class "Default")
      (node (ref "J17") (pin "2") (pinfunction "2_2") (pintype "passive"))
      (node (ref "J2") (pin "41") (pinfunction "41_41") (pintype "passive"))
    )
    (net (code "41") (name "/PWM5") (class "Default")
      (node (ref "J18") (pin "2") (pinfunction "2_2") (pintype "passive"))
      (node (ref "J2") (pin "43") (pinfunction "43_43") (pintype "passive"))
    )
    (net (code "42") (name "/PWM6") (class "Default")
      (node (ref "J2") (pin "51") (pinfunction "51_51") (pintype "passive"))
    )
    (net (code "43") (name "/PWM7") (class "Default")
      (node (ref "J2") (pin "55") (pinfunction "55_55") (pintype "passive"))
    )
    (net (code "44") (name "/SPI1_CS") (class "Default")
      (node (ref "J1") (pin "66") (pinfunction "66_66") (pintype "passive"))
      (node (ref "J26") (pin "4") (pinfunction "4_4") (pintype "passive"))
    )
    (net (code "45") (name "/SPI1_MISO") (class "Default")
      (node (ref "J1") (pin "63") (pinfunction "63_63") (pintype "passive"))
      (node (ref "J26") (pin "3") (pinfunction "3_3") (pintype "passive"))
    )
    (net (code "46") (name "/SPI1_MOSI") (class "Default")
      (node (ref "J1") (pin "45") (pinfunction "45_45") (pintype "passive"))
      (node (ref "J26") (pin "2") (pinfunction "2_2") (pintype "passive"))
    )
    (net (code "47") (name "/SPI1_SCK") (class "Default")
      (node (ref "J1") (pin "70") (pinfunction "70_70") (pintype "passive"))
      (node (ref "J26") (pin "1") (pinfunction "1_1") (pintype "passive"))
    )
    (net (code "48") (name "/SPI2_CS") (class "Default")
      (node (ref "J2") (pin "27") (pinfunction "27_27") (pintype "passive"))
      (node (ref "J27") (pin "4") (pinfunction "4_4") (pintype "passive"))
    )
    (net (code "49") (name "/SPI2_MISO") (class "Default")
      (node (ref "J1") (pin "35") (pinfunction "35_35") (pintype "passive"))
      (node (ref "J27") (pin "3") (pinfunction "3_3") (pintype "passive"))
    )
    (net (code "50") (name "/SPI2_MOSI") (class "Default")
      (node (ref "J1") (pin "37") (pinfunction "37_37") (pintype "passive"))
      (node (ref "J27") (pin "2") (pinfunction "2_2") (pintype "passive"))
    )
    (net (code "51") (name "/SPI2_SCK") (class "Default")
      (node (ref "J1") (pin "40") (pinfunction "40_40") (pintype "passive"))
      (node (ref "J27") (pin "1") (pinfunction "1_1") (pintype "passive"))
    )
    (net (code "52") (name "/SPI3_CS") (class "Default")
      (node (ref "J1") (pin "32") (pinfunction "32_32") (pintype "passive"))
      (node (ref "J28") (pin "4") (pinfunction "4_4") (pintype "passive"))
    )
    (net (code "53") (name "/SPI3_MISO") (class "Default")
      (node (ref "J1") (pin "02") (pinfunction "02_02") (pintype "passive"))
      (node (ref "J28") (pin "3") (pinfunction "3_3") (pintype "passive"))
    )
    (net (code "54") (name "/SPI3_MOSI") (class "Default")
      (node (ref "J1") (pin "43") (pinfunction "43_43") (pintype "passive"))
      (node (ref "J28") (pin "2") (pinfunction "2_2") (pintype "passive"))
    )
    (net (code "55") (name "/SPI3_SCK") (class "Default")
      (node (ref "J1") (pin "01") (pinfunction "01_01") (pintype "passive"))
      (node (ref "J28") (pin "1") (pinfunction "1_1") (pintype "passive"))
    )
    (net (code "56") (name "/SPI4_CS") (class "Default")
      (node (ref "J1") (pin "48") (pinfunction "48_48") (pintype "passive"))
      (node (ref "J32") (pin "4") (pinfunction "4_4") (pintype "passive"))
    )
    (net (code "57") (name "/SPI4_MISO") (class "Default")
      (node (ref "J1") (pin "50") (pinfunction "50_50") (pintype "passive"))
      (node (ref "J32") (pin "3") (pinfunction "3_3") (pintype "passive"))
    )
    (net (code "58") (name "/SPI4_MOSI") (class "Default")
      (node (ref "J1") (pin "62") (pinfunction "62_62") (pintype "passive"))
      (node (ref "J32") (pin "2") (pinfunction "2_2") (pintype "passive"))
    )
    (net (code "59") (name "/SPI4_SCK") (class "Default")
      (node (ref "J1") (pin "46") (pinfunction "46_46") (pintype "passive"))
      (node (ref "J32") (pin "1") (pinfunction "1_1") (pintype "passive"))
    )
    (net (code "60") (name "/SPI5_CS") (class "Default")
      (node (ref "J1") (pin "09") (pinfunction "09_09") (pintype "passive"))
      (node (ref "J33") (pin "4") (pinfunction "4_4") (pintype "passive"))
    )
    (net (code "61") (name "/SPI5_MISO") (class "Default")
      (node (ref "J1") (pin "54") (pinfunction "54_54") (pintype "passive"))
      (node (ref "J33") (pin "3") (pinfunction "3_3") (pintype "passive"))
    )
    (net (code "62") (name "/SPI5_MOSI") (class "Default")
      (node (ref "J1") (pin "56") (pinfunction "56_56") (pintype "passive"))
      (node (ref "J33") (pin "2") (pinfunction "2_2") (pintype "passive"))
    )
    (net (code "63") (name "/SPI5_SCK") (class "Default")
      (node (ref "J1") (pin "11") (pinfunction "11_11") (pintype "passive"))
      (node (ref "J33") (pin "1") (pinfunction "1_1") (pintype "passive"))
    )
    (net (code "64") (name "/SPI6_CS") (class "Default")
      (node (ref "J2") (pin "66") (pinfunction "66_66") (pintype "passive"))
      (node (ref "J34") (pin "4") (pinfunction "4_4") (pintype "passive"))
    )
    (net (code "65") (name "/SPI6_MISO") (class "Default")
      (node (ref "J1") (pin "65") (pinfunction "65_65") (pintype "passive"))
      (node (ref "J34") (pin "3") (pinfunction "3_3") (pintype "passive"))
    )
    (net (code "66") (name "/SPI6_MOSI") (class "Default")
      (node (ref "J2") (pin "61") (pinfunction "61_61") (pintype "passive"))
      (node (ref "J34") (pin "2") (pinfunction "2_2") (pintype "passive"))
    )
    (net (code "67") (name "/SPI6_SCK") (class "Default")
      (node (ref "J1") (pin "68") (pinfunction "68_68") (pintype "passive"))
      (node (ref "J34") (pin "1") (pinfunction "1_1") (pintype "passive"))
    )
    (net (code "68") (name "/UART5_RX") (class "Default")
      (node (ref "J1") (pin "04") (pinfunction "04_04") (pintype "passive"))
      (node (ref "U3") (pin "12") (pinfunction "ROUT1_12") (pintype "output"))
    )
    (net (code "69") (name "/UART5_TX") (class "Default")
      (node (ref "J1") (pin "03") (pinfunction "03_03") (pintype "passive"))
      (node (ref "U3") (pin "11") (pinfunction "DIN1_11") (pintype "input"))
    )
    (net (code "70") (name "/UART7_RX") (class "Default")
      (node (ref "J2") (pin "44") (pinfunction "44_44") (pintype "passive"))
      (node (ref "J24") (pin "2") (pinfunction "2_2") (pintype "passive"))
    )
    (net (code "71") (name "/UART7_TX") (class "Default")
      (node (ref "J2") (pin "40") (pinfunction "40_40") (pintype "passive"))
      (node (ref "J24") (pin "1") (pinfunction "1_1") (pintype "passive"))
    )
    (net (code "72") (name "/UART8_RX") (class "Default")
      (node (ref "J2") (pin "64") (pinfunction "64_64") (pintype "passive"))
      (node (ref "J25") (pin "2") (pinfunction "2_2") (pintype "passive"))
    )
    (net (code "73") (name "/UART8_TX") (class "Default")
      (node (ref "J1") (pin "61") (pinfunction "61_61") (pintype "passive"))
      (node (ref "J25") (pin "1") (pinfunction "1_1") (pintype "passive"))
    )
    (net (code "74") (name "3V3") (class "Default")
      (node (ref "C2") (pin "2") (pinfunction "2_2") (pintype "passive"))
      (node (ref "C4") (pin "2") (pinfunction "2_2") (pintype "passive"))
      (node (ref "C5") (pin "2") (pinfunction "2_2") (pintype "passive"))
      (node (ref "J1") (pin "16") (pinfunction "16_16") (pintype "passive"))
      (node (ref "R1") (pin "2") (pinfunction "2_2") (pintype "passive"))
      (node (ref "R14") (pin "1") (pinfunction "1_1") (pintype "passive"))
      (node (ref "R15") (pin "1") (pinfunction "1_1") (pintype "passive"))
      (node (ref "R18") (pin "1") (pinfunction "1_1") (pintype "passive"))
      (node (ref "R5") (pin "2") (pinfunction "2_2") (pintype "passive"))
      (node (ref "U1") (pin "3") (pinfunction "VCC_3") (pintype "power_in"))
      (node (ref "U2") (pin "3") (pinfunction "VCC_3") (pintype "power_in"))
      (node (ref "U3") (pin "16") (pinfunction "VCC_16") (pintype "power_in"))
    )
    (net (code "75") (name "5V") (class "Default")
      (node (ref "J1") (pin "18") (pinfunction "18_18") (pintype "passive"))
      (node (ref "R12") (pin "1") (pinfunction "1_1") (pintype "passive"))
      (node (ref "R13") (pin "1") (pinfunction "1_1") (pintype "passive"))
      (node (ref "R17") (pin "1") (pinfunction "1_1") (pintype "passive"))
    )
    (net (code "76") (name "GND") (class "Default")
      (node (ref "C1") (pin "2") (pinfunction "2_2") (pintype "passive"))
      (node (ref "C2") (pin "1") (pinfunction "1_1") (pintype "passive"))
      (node (ref "C3") (pin "2") (pinfunction "2_2") (pintype "passive"))
      (node (ref "C4") (pin "1") (pinfunction "1_1") (pintype "passive"))
      (node (ref "C5") (pin "1") (pinfunction "1_1") (pintype "passive"))
      (node (ref "C7") (pin "1") (pinfunction "1_1") (pintype "passive"))
      (node (ref "C8") (pin "1") (pinfunction "1_1") (pintype "passive"))
      (node (ref "D1") (pin "2") (pinfunction "2_2") (pintype "passive"))
      (node (ref "J1") (pin "08") (pinfunction "08_08") (pintype "passive"))
      (node (ref "J1") (pin "19") (pinfunction "19_19") (pintype "passive"))
      (node (ref "J1") (pin "20") (pinfunction "20_20") (pintype "passive"))
      (node (ref "J1") (pin "22") (pinfunction "22_22") (pintype "passive"))
      (node (ref "J1") (pin "49") (pinfunction "49_49") (pintype "passive"))
      (node (ref "J1") (pin "60") (pinfunction "60_60") (pintype "passive"))
      (node (ref "J10") (pin "6") (pinfunction "6_6") (pintype "passive"))
      (node (ref "J11") (pin "3") (pinfunction "3_3") (pintype "passive"))
      (node (ref "J12") (pin "3") (pinfunction "3_3") (pintype "passive"))
      (node (ref "J13") (pin "3") (pinfunction "3_3") (pintype "passive"))
      (node (ref "J14") (pin "3") (pinfunction "3_3") (pintype "passive"))
      (node (ref "J15") (pin "3") (pinfunction "3_3") (pintype "passive"))
      (node (ref "J16") (pin "3") (pinfunction "3_3") (pintype "passive"))
      (node (ref "J17") (pin "3") (pinfunction "3_3") (pintype "passive"))
      (node (ref "J18") (pin "3") (pinfunction "3_3") (pintype "passive"))
      (node (ref "J19") (pin "3") (pinfunction "3_3") (pintype "passive"))
      (node (ref "J2") (pin "09") (pinfunction "09_09") (pintype "passive"))
      (node (ref "J2") (pin "20") (pinfunction "20_20") (pintype "passive"))
      (node (ref "J2") (pin "39") (pinfunction "39_39") (pintype "passive"))
      (node (ref "J2") (pin "54") (pinfunction "54_54") (pintype "passive"))
      (node (ref "J2") (pin "63") (pinfunction "63_63") (pintype "passive"))
      (node (ref "J20") (pin "3") (pinfunction "3_3") (pintype "passive"))
      (node (ref "J21") (pin "6") (pinfunction "6_6") (pintype "passive"))
      (node (ref "J22") (pin "6") (pinfunction "6_6") (pintype "passive"))
      (node (ref "J23") (pin "3") (pinfunction "3_3") (pintype "passive"))
      (node (ref "J24") (pin "3") (pinfunction "3_3") (pintype "passive"))
      (node (ref "J25") (pin "3") (pinfunction "3_3") (pintype "passive"))
      (node (ref "J29") (pin "4") (pinfunction "4_4") (pintype "passive"))
      (node (ref "J3") (pin "S1") (pinfunction "SHIELD_S1") (pintype "passive"))
      (node (ref "J3") (pin "S2") (pinfunction "SHIELD_S2") (pintype "passive"))
      (node (ref "J30") (pin "4") (pinfunction "4_4") (pintype "passive"))
      (node (ref "J31") (pin "1") (pinfunction "NEG_1") (pintype "passive"))
      (node (ref "J35") (pin "4") (pinfunction "4_4") (pintype "passive"))
      (node (ref "J36") (pin "4") (pinfunction "4_4") (pintype "passive"))
      (node (ref "J4") (pin "S1") (pinfunction "SHIELD_S1") (pintype "passive"))
      (node (ref "J4") (pin "S2") (pinfunction "SHIELD_S2") (pintype "passive"))
      (node (ref "J5") (pin "3") (pinfunction "3_3") (pintype "passive"))
      (node (ref "J6") (pin "3") (pinfunction "3_3") (pintype "passive"))
      (node (ref "J7") (pin "5") (pinfunction "5_5") (pintype "passive"))
      (node (ref "J7") (pin "S1") (pinfunction "SHIELD_S1") (pintype "passive"))
      (node (ref "J7") (pin "S2") (pinfunction "SHIELD_S2") (pintype "passive"))
      (node (ref "J8") (pin "3") (pinfunction "3_3") (pintype "passive"))
      (node (ref "J9") (pin "3") (pinfunction "3_3") (pintype "passive"))
      (node (ref "R3") (pin "1") (pinfunction "1_1") (pintype "passive"))
      (node (ref "R7") (pin "1") (pinfunction "1_1") (pintype "passive"))
      (node (ref "U1") (pin "2") (pinfunction "GND_2") (pintype "power_in"))
      (node (ref "U2") (pin "2") (pinfunction "GND_2") (pintype "power_in"))
      (node (ref "U3") (pin "15") (pinfunction "GND_15") (pintype "power_in"))
    )
    (net (code "77") (name "Net-(D1-Pad1)") (class "Default")
      (node (ref "D1") (pin "1") (pinfunction "1_1") (pintype "passive"))
      (node (ref "R10") (pin "2") (pinfunction "2_2") (pintype "passive"))
    )
    (net (code "78") (name "Net-(U1-RS)") (class "Default")
      (node (ref "R1") (pin "1") (pinfunction "1_1") (pintype "passive"))
      (node (ref "R3") (pin "2") (pinfunction "2_2") (pintype "passive"))
      (node (ref "U1") (pin "8") (pinfunction "RS_8") (pintype "input"))
    )
    (net (code "79") (name "Net-(U1-VREF)") (class "Default")
      (node (ref "C1") (pin "1") (pinfunction "1_1") (pintype "passive"))
      (node (ref "R2") (pin "2") (pinfunction "2_2") (pintype "passive"))
      (node (ref "R4") (pin "1") (pinfunction "1_1") (pintype "passive"))
      (node (ref "U1") (pin "5") (pinfunction "VREF_5") (pintype "output"))
    )
    (net (code "80") (name "Net-(U2-RS)") (class "Default")
      (node (ref "R5") (pin "1") (pinfunction "1_1") (pintype "passive"))
      (node (ref "R7") (pin "2") (pinfunction "2_2") (pintype "passive"))
      (node (ref "U2") (pin "8") (pinfunction "RS_8") (pintype "input"))
    )
    (net (code "81") (name "Net-(U2-VREF)") (class "Default")
      (node (ref "C3") (pin "1") (pinfunction "1_1") (pintype "passive"))
      (node (ref "R6") (pin "2") (pinfunction "2_2") (pintype "passive"))
      (node (ref "R8") (pin "1") (pinfunction "1_1") (pintype "passive"))
      (node (ref "U2") (pin "5") (pinfunction "VREF_5") (pintype "output"))
    )
    (net (code "82") (name "Net-(U3-C1+)") (class "Default")
      (node (ref "C6") (pin "2") (pinfunction "2_2") (pintype "passive"))
      (node (ref "U3") (pin "1") (pinfunction "C1+_1") (pintype "passive"))
    )
    (net (code "83") (name "Net-(U3-C1-)") (class "Default")
      (node (ref "C6") (pin "1") (pinfunction "1_1") (pintype "passive"))
      (node (ref "U3") (pin "3") (pinfunction "C1-_3") (pintype "passive"))
    )
    (net (code "84") (name "Net-(U3-C2+)") (class "Default")
      (node (ref "C9") (pin "2") (pinfunction "2_2") (pintype "passive"))
      (node (ref "U3") (pin "4") (pinfunction "C2+_4") (pintype "passive"))
    )
    (net (code "85") (name "Net-(U3-C2-)") (class "Default")
      (node (ref "C9") (pin "1") (pinfunction "1_1") (pintype "passive"))
      (node (ref "U3") (pin "5") (pinfunction "C2-_5") (pintype "passive"))
    )
    (net (code "86") (name "Net-(U3-DOUT1)") (class "Default")
      (node (ref "J7") (pin "2") (pinfunction "2_2") (pintype "passive"))
      (node (ref "U3") (pin "14") (pinfunction "DOUT1_14") (pintype "output"))
    )
    (net (code "87") (name "Net-(U3-RIN1)") (class "Default")
      (node (ref "J7") (pin "3") (pinfunction "3_3") (pintype "passive"))
      (node (ref "U3") (pin "13") (pinfunction "RIN1_13") (pintype "input"))
    )
    (net (code "88") (name "Net-(U3-V+)") (class "Default")
      (node (ref "C7") (pin "2") (pinfunction "2_2") (pintype "passive"))
      (node (ref "U3") (pin "2") (pinfunction "V+_2") (pintype "output"))
    )
    (net (code "89") (name "Net-(U3-V-)") (class "Default")
      (node (ref "C8") (pin "2") (pinfunction "2_2") (pintype "passive"))
      (node (ref "U3") (pin "6") (pinfunction "V-_6") (pintype "output"))
    )
    (net (code "90") (name "VADC") (class "Default")
      (node (ref "J11") (pin "1") (pinfunction "1_1") (pintype "passive"))
      (node (ref "J12") (pin "1") (pinfunction "1_1") (pintype "passive"))
      (node (ref "J15") (pin "1") (pinfunction "1_1") (pintype "passive"))
      (node (ref "J16") (pin "1") (pinfunction "1_1") (pintype "passive"))
      (node (ref "J19") (pin "1") (pinfunction "1_1") (pintype "passive"))
      (node (ref "J20") (pin "1") (pinfunction "1_1") (pintype "passive"))
      (node (ref "J23") (pin "1") (pinfunction "1_1") (pintype "passive"))
      (node (ref "J5") (pin "1") (pinfunction "1_1") (pintype "passive"))
      (node (ref "J6") (pin "1") (pinfunction "1_1") (pintype "passive"))
      (node (ref "R16") (pin "2") (pinfunction "2_2") (pintype "passive"))
      (node (ref "R17") (pin "2") (pinfunction "2_2") (pintype "passive"))
      (node (ref "R18") (pin "2") (pinfunction "2_2") (pintype "passive"))
    )
    (net (code "91") (name "VI2C") (class "Default")
      (node (ref "J29") (pin "1") (pinfunction "1_1") (pintype "passive"))
      (node (ref "J30") (pin "1") (pinfunction "1_1") (pintype "passive"))
      (node (ref "J36") (pin "1") (pinfunction "1_1") (pintype "passive"))
      (node (ref "R11") (pin "2") (pinfunction "2_2") (pintype "passive"))
      (node (ref "R13") (pin "2") (pinfunction "2_2") (pintype "passive"))
      (node (ref "R15") (pin "2") (pinfunction "2_2") (pintype "passive"))
    )
    (net (code "92") (name "VIN") (class "Default")
      (node (ref "J1") (pin "24") (pinfunction "24_24") (pintype "passive"))
      (node (ref "J31") (pin "2") (pinfunction "POS_2") (pintype "passive"))
      (node (ref "R10") (pin "1") (pinfunction "1_1") (pintype "passive"))
      (node (ref "R11") (pin "1") (pinfunction "1_1") (pintype "passive"))
      (node (ref "R16") (pin "1") (pinfunction "1_1") (pintype "passive"))
      (node (ref "R9") (pin "1") (pinfunction "1_1") (pintype "passive"))
    )
    (net (code "93") (name "VPWM") (class "Default")
      (node (ref "J10") (pin "4") (pinfunction "4_4") (pintype "passive"))
      (node (ref "J13") (pin "1") (pinfunction "1_1") (pintype "passive"))
      (node (ref "J14") (pin "1") (pinfunction "1_1") (pintype "passive"))
      (node (ref "J17") (pin "1") (pinfunction "1_1") (pintype "passive"))
      (node (ref "J18") (pin "1") (pinfunction "1_1") (pintype "passive"))
      (node (ref "J21") (pin "4") (pinfunction "4_4") (pintype "passive"))
      (node (ref "J22") (pin "4") (pinfunction "4_4") (pintype "passive"))
      (node (ref "J8") (pin "1") (pinfunction "1_1") (pintype "passive"))
      (node (ref "J9") (pin "1") (pinfunction "1_1") (pintype "passive"))
      (node (ref "R12") (pin "2") (pinfunction "2_2") (pintype "passive"))
      (node (ref "R14") (pin "2") (pinfunction "2_2") (pintype "passive"))
      (node (ref "R9") (pin "2") (pinfunction "2_2") (pintype "passive"))
    )
    (net (code "94") (name "unconnected-(J1-Pad05)") (class "Default")
      (node (ref "J1") (pin "05") (pinfunction "05_05") (pintype "passive+no_connect"))
    )
    (net (code "95") (name "unconnected-(J1-Pad06)") (class "Default")
      (node (ref "J1") (pin "06") (pinfunction "06_06") (pintype "passive"))
    )
    (net (code "96") (name "unconnected-(J1-Pad07)") (class "Default")
      (node (ref "J1") (pin "07") (pinfunction "07_07") (pintype "passive+no_connect"))
    )
    (net (code "97") (name "unconnected-(J1-Pad10)") (class "Default")
      (node (ref "J1") (pin "10") (pinfunction "10_10") (pintype "passive+no_connect"))
    )
    (net (code "98") (name "unconnected-(J1-Pad12)") (class "Default")
      (node (ref "J1") (pin "12") (pinfunction "12_12") (pintype "passive"))
    )
    (net (code "99") (name "unconnected-(J1-Pad13)") (class "Default")
      (node (ref "J1") (pin "13") (pinfunction "13_13") (pintype "passive+no_connect"))
    )
    (net (code "100") (name "unconnected-(J1-Pad14)") (class "Default")
      (node (ref "J1") (pin "14") (pinfunction "14_14") (pintype "passive"))
    )
    (net (code "101") (name "unconnected-(J1-Pad15)") (class "Default")
      (node (ref "J1") (pin "15") (pinfunction "15_15") (pintype "passive+no_connect"))
    )
    (net (code "102") (name "unconnected-(J1-Pad17)") (class "Default")
      (node (ref "J1") (pin "17") (pinfunction "17_17") (pintype "passive+no_connect"))
    )
    (net (code "103") (name "unconnected-(J1-Pad21)") (class "Default")
      (node (ref "J1") (pin "21") (pinfunction "21_21") (pintype "passive+no_connect"))
    )
    (net (code "104") (name "unconnected-(J1-Pad23)") (class "Default")
      (node (ref "J1") (pin "23") (pinfunction "23_23") (pintype "passive+no_connect"))
    )
    (net (code "105") (name "unconnected-(J1-Pad25)") (class "Default")
      (node (ref "J1") (pin "25") (pinfunction "25_25") (pintype "passive+no_connect"))
    )
    (net (code "106") (name "unconnected-(J1-Pad26)") (class "Default")
      (node (ref "J1") (pin "26") (pinfunction "26_26") (pintype "passive+no_connect"))
    )
    (net (code "107") (name "unconnected-(J1-Pad27)") (class "Default")
      (node (ref "J1") (pin "27") (pinfunction "27_27") (pintype "passive+no_connect"))
    )
    (net (code "108") (name "unconnected-(J1-Pad28)") (class "Default")
      (node (ref "J1") (pin "28") (pinfunction "28_28") (pintype "passive+no_connect"))
    )
    (net (code "109") (name "unconnected-(J1-Pad29)") (class "Default")
      (node (ref "J1") (pin "29") (pinfunction "29_29") (pintype "passive+no_connect"))
    )
    (net (code "110") (name "unconnected-(J1-Pad30)") (class "Default")
      (node (ref "J1") (pin "30") (pinfunction "30_30") (pintype "passive+no_connect"))
    )
    (net (code "111") (name "unconnected-(J1-Pad31)") (class "Default")
      (node (ref "J1") (pin "31") (pinfunction "31_31") (pintype "passive+no_connect"))
    )
    (net (code "112") (name "unconnected-(J1-Pad33)") (class "Default")
      (node (ref "J1") (pin "33") (pinfunction "33_33") (pintype "passive+no_connect"))
    )
    (net (code "113") (name "unconnected-(J1-Pad34)") (class "Default")
      (node (ref "J1") (pin "34") (pinfunction "34_34") (pintype "passive+no_connect"))
    )
    (net (code "114") (name "unconnected-(J1-Pad36)") (class "Default")
      (node (ref "J1") (pin "36") (pinfunction "36_36") (pintype "passive+no_connect"))
    )
    (net (code "115") (name "unconnected-(J1-Pad39)") (class "Default")
      (node (ref "J1") (pin "39") (pinfunction "39_39") (pintype "passive+no_connect"))
    )
    (net (code "116") (name "unconnected-(J1-Pad41)") (class "Default")
      (node (ref "J1") (pin "41") (pinfunction "41_41") (pintype "passive+no_connect"))
    )
    (net (code "117") (name "unconnected-(J1-Pad42)") (class "Default")
      (node (ref "J1") (pin "42") (pinfunction "42_42") (pintype "passive+no_connect"))
    )
    (net (code "118") (name "unconnected-(J1-Pad44)") (class "Default")
      (node (ref "J1") (pin "44") (pinfunction "44_44") (pintype "passive+no_connect"))
    )
    (net (code "119") (name "unconnected-(J1-Pad47)") (class "Default")
      (node (ref "J1") (pin "47") (pinfunction "47_47") (pintype "passive+no_connect"))
    )
    (net (code "120") (name "unconnected-(J1-Pad52)") (class "Default")
      (node (ref "J1") (pin "52") (pinfunction "52_52") (pintype "passive+no_connect"))
    )
    (net (code "121") (name "unconnected-(J1-Pad58)") (class "Default")
      (node (ref "J1") (pin "58") (pinfunction "58_58") (pintype "passive+no_connect"))
    )
    (net (code "122") (name "unconnected-(J1-Pad59)") (class "Default")
      (node (ref "J1") (pin "59") (pinfunction "59_59") (pintype "passive+no_connect"))
    )
    (net (code "123") (name "unconnected-(J1-Pad64)") (class "Default")
      (node (ref "J1") (pin "64") (pinfunction "64_64") (pintype "passive+no_connect"))
    )
    (net (code "124") (name "unconnected-(J1-Pad67)") (class "Default")
      (node (ref "J1") (pin "67") (pinfunction "67_67") (pintype "passive+no_connect"))
    )
    (net (code "125") (name "unconnected-(J1-Pad69)") (class "Default")
      (node (ref "J1") (pin "69") (pinfunction "69_69") (pintype "passive+no_connect"))
    )
    (net (code "126") (name "unconnected-(J2-Pad07)") (class "Default")
      (node (ref "J2") (pin "07") (pinfunction "07_07") (pintype "passive+no_connect"))
    )
    (net (code "127") (name "unconnected-(J2-Pad08)") (class "Default")
      (node (ref "J2") (pin "08") (pinfunction "08_08") (pintype "passive+no_connect"))
    )
    (net (code "128") (name "unconnected-(J2-Pad15)") (class "Default")
      (node (ref "J2") (pin "15") (pinfunction "15_15") (pintype "passive+no_connect"))
    )
    (net (code "129") (name "unconnected-(J2-Pad21)") (class "Default")
      (node (ref "J2") (pin "21") (pinfunction "21_21") (pintype "passive+no_connect"))
    )
    (net (code "130") (name "unconnected-(J2-Pad26)") (class "Default")
      (node (ref "J2") (pin "26") (pinfunction "26_26") (pintype "passive+no_connect"))
    )
    (net (code "131") (name "unconnected-(J2-Pad28)") (class "Default")
      (node (ref "J2") (pin "28") (pinfunction "28_28") (pintype "passive+no_connect"))
    )
    (net (code "132") (name "unconnected-(J2-Pad30)") (class "Default")
      (node (ref "J2") (pin "30") (pinfunction "30_30") (pintype "passive+no_connect"))
    )
    (net (code "133") (name "unconnected-(J2-Pad31)") (class "Default")
      (node (ref "J2") (pin "31") (pinfunction "31_31") (pintype "passive+no_connect"))
    )
    (net (code "134") (name "unconnected-(J2-Pad32)") (class "Default")
      (node (ref "J2") (pin "32") (pinfunction "32_32") (pintype "passive+no_connect"))
    )
    (net (code "135") (name "unconnected-(J2-Pad33)") (class "Default")
      (node (ref "J2") (pin "33") (pinfunction "33_33") (pintype "passive+no_connect"))
    )
    (net (code "136") (name "unconnected-(J2-Pad34)") (class "Default")
      (node (ref "J2") (pin "34") (pinfunction "34_34") (pintype "passive+no_connect"))
    )
    (net (code "137") (name "unconnected-(J2-Pad35)") (class "Default")
      (node (ref "J2") (pin "35") (pinfunction "35_35") (pintype "passive+no_connect"))
    )
    (net (code "138") (name "unconnected-(J2-Pad45)") (class "Default")
      (node (ref "J2") (pin "45") (pinfunction "45_45") (pintype "passive+no_connect"))
    )
    (net (code "139") (name "unconnected-(J2-Pad46)") (class "Default")
      (node (ref "J2") (pin "46") (pinfunction "46_46") (pintype "passive+no_connect"))
    )
    (net (code "140") (name "unconnected-(J2-Pad47)") (class "Default")
      (node (ref "J2") (pin "47") (pinfunction "47_47") (pintype "passive+no_connect"))
    )
    (net (code "141") (name "unconnected-(J2-Pad48)") (class "Default")
      (node (ref "J2") (pin "48") (pinfunction "48_48") (pintype "passive+no_connect"))
    )
    (net (code "142") (name "unconnected-(J2-Pad49)") (class "Default")
      (node (ref "J2") (pin "49") (pinfunction "49_49") (pintype "passive+no_connect"))
    )
    (net (code "143") (name "unconnected-(J2-Pad52)") (class "Default")
      (node (ref "J2") (pin "52") (pinfunction "52_52") (pintype "passive+no_connect"))
    )
    (net (code "144") (name "unconnected-(J2-Pad53)") (class "Default")
      (node (ref "J2") (pin "53") (pinfunction "53_53") (pintype "passive+no_connect"))
    )
    (net (code "145") (name "unconnected-(J2-Pad56)") (class "Default")
      (node (ref "J2") (pin "56") (pinfunction "56_56") (pintype "passive+no_connect"))
    )
    (net (code "146") (name "unconnected-(J2-Pad62)") (class "Default")
      (node (ref "J2") (pin "62") (pinfunction "62_62") (pintype "passive+no_connect"))
    )
    (net (code "147") (name "unconnected-(J2-Pad65)") (class "Default")
      (node (ref "J2") (pin "65") (pinfunction "65_65") (pintype "passive+no_connect"))
    )
    (net (code "148") (name "unconnected-(J2-Pad67)") (class "Default")
      (node (ref "J2") (pin "67") (pinfunction "67_67") (pintype "passive+no_connect"))
    )
    (net (code "149") (name "unconnected-(J2-Pad68)") (class "Default")
      (node (ref "J2") (pin "68") (pinfunction "68_68") (pintype "passive+no_connect"))
    )
    (net (code "150") (name "unconnected-(J2-Pad69)") (class "Default")
      (node (ref "J2") (pin "69") (pinfunction "69_69") (pintype "passive+no_connect"))
    )
    (net (code "151") (name "unconnected-(J2-Pad70)") (class "Default")
      (node (ref "J2") (pin "70") (pinfunction "70_70") (pintype "passive+no_connect"))
    )
    (net (code "152") (name "unconnected-(J3-Pad1)") (class "Default")
      (node (ref "J3") (pin "1") (pinfunction "1_1") (pintype "passive"))
    )
    (net (code "153") (name "unconnected-(J3-Pad3)") (class "Default")
      (node (ref "J3") (pin "3") (pinfunction "3_3") (pintype "passive"))
    )
    (net (code "154") (name "unconnected-(J3-Pad4)") (class "Default")
      (node (ref "J3") (pin "4") (pinfunction "4_4") (pintype "passive"))
    )
    (net (code "155") (name "unconnected-(J3-Pad5)") (class "Default")
      (node (ref "J3") (pin "5") (pinfunction "5_5") (pintype "passive"))
    )
    (net (code "156") (name "unconnected-(J3-Pad6)") (class "Default")
      (node (ref "J3") (pin "6") (pinfunction "6_6") (pintype "passive"))
    )
    (net (code "157") (name "unconnected-(J3-Pad8)") (class "Default")
      (node (ref "J3") (pin "8") (pinfunction "8_8") (pintype "passive"))
    )
    (net (code "158") (name "unconnected-(J3-Pad9)") (class "Default")
      (node (ref "J3") (pin "9") (pinfunction "9_9") (pintype "passive"))
    )
    (net (code "159") (name "unconnected-(J4-Pad1)") (class "Default")
      (node (ref "J4") (pin "1") (pinfunction "1_1") (pintype "passive"))
    )
    (net (code "160") (name "unconnected-(J4-Pad3)") (class "Default")
      (node (ref "J4") (pin "3") (pinfunction "3_3") (pintype "passive"))
    )
    (net (code "161") (name "unconnected-(J4-Pad4)") (class "Default")
      (node (ref "J4") (pin "4") (pinfunction "4_4") (pintype "passive"))
    )
    (net (code "162") (name "unconnected-(J4-Pad5)") (class "Default")
      (node (ref "J4") (pin "5") (pinfunction "5_5") (pintype "passive"))
    )
    (net (code "163") (name "unconnected-(J4-Pad6)") (class "Default")
      (node (ref "J4") (pin "6") (pinfunction "6_6") (pintype "passive"))
    )
    (net (code "164") (name "unconnected-(J4-Pad8)") (class "Default")
      (node (ref "J4") (pin "8") (pinfunction "8_8") (pintype "passive"))
    )
    (net (code "165") (name "unconnected-(J4-Pad9)") (class "Default")
      (node (ref "J4") (pin "9") (pinfunction "9_9") (pintype "passive"))
    )
    (net (code "166") (name "unconnected-(J7-Pad1)") (class "Default")
      (node (ref "J7") (pin "1") (pinfunction "1_1") (pintype "passive"))
    )
    (net (code "167") (name "unconnected-(J7-Pad4)") (class "Default")
      (node (ref "J7") (pin "4") (pinfunction "4_4") (pintype "passive"))
    )
    (net (code "168") (name "unconnected-(J7-Pad6)") (class "Default")
      (node (ref "J7") (pin "6") (pinfunction "6_6") (pintype "passive"))
    )
    (net (code "169") (name "unconnected-(J7-Pad7)") (class "Default")
      (node (ref "J7") (pin "7") (pinfunction "7_7") (pintype "passive"))
    )
    (net (code "170") (name "unconnected-(J7-Pad8)") (class "Default")
      (node (ref "J7") (pin "8") (pinfunction "8_8") (pintype "passive"))
    )
    (net (code "171") (name "unconnected-(J7-Pad9)") (class "Default")
      (node (ref "J7") (pin "9") (pinfunction "9_9") (pintype "passive"))
    )
    (net (code "172") (name "unconnected-(J10-Pad5)") (class "Default")
      (node (ref "J10") (pin "5") (pinfunction "5_5") (pintype "passive"))
    )
    (net (code "173") (name "unconnected-(J21-Pad5)") (class "Default")
      (node (ref "J21") (pin "5") (pinfunction "5_5") (pintype "passive"))
    )
    (net (code "174") (name "unconnected-(J22-Pad5)") (class "Default")
      (node (ref "J22") (pin "5") (pinfunction "5_5") (pintype "passive"))
    )
    (net (code "175") (name "unconnected-(J35-Pad1)") (class "Default")
      (node (ref "J35") (pin "1") (pinfunction "1_1") (pintype "passive"))
    )
    (net (code "176") (name "unconnected-(U3-DIN2-Pad10)") (class "Default")
      (node (ref "U3") (pin "10") (pinfunction "DIN2_10") (pintype "input+no_connect"))
    )
    (net (code "177") (name "unconnected-(U3-DOUT2-Pad7)") (class "Default")
      (node (ref "U3") (pin "7") (pinfunction "DOUT2_7") (pintype "output+no_connect"))
    )
    (net (code "178") (name "unconnected-(U3-RIN2-Pad8)") (class "Default")
      (node (ref "U3") (pin "8") (pinfunction "RIN2_8") (pintype "input+no_connect"))
    )
    (net (code "179") (name "unconnected-(U3-ROUT2-Pad9)") (class "Default")
      (node (ref "U3") (pin "9") (pinfunction "ROUT2_9") (pintype "output+no_connect"))
    )
  )
)
